# Audio.net
KiCad netlist of a schematic drawn in Altium Designer
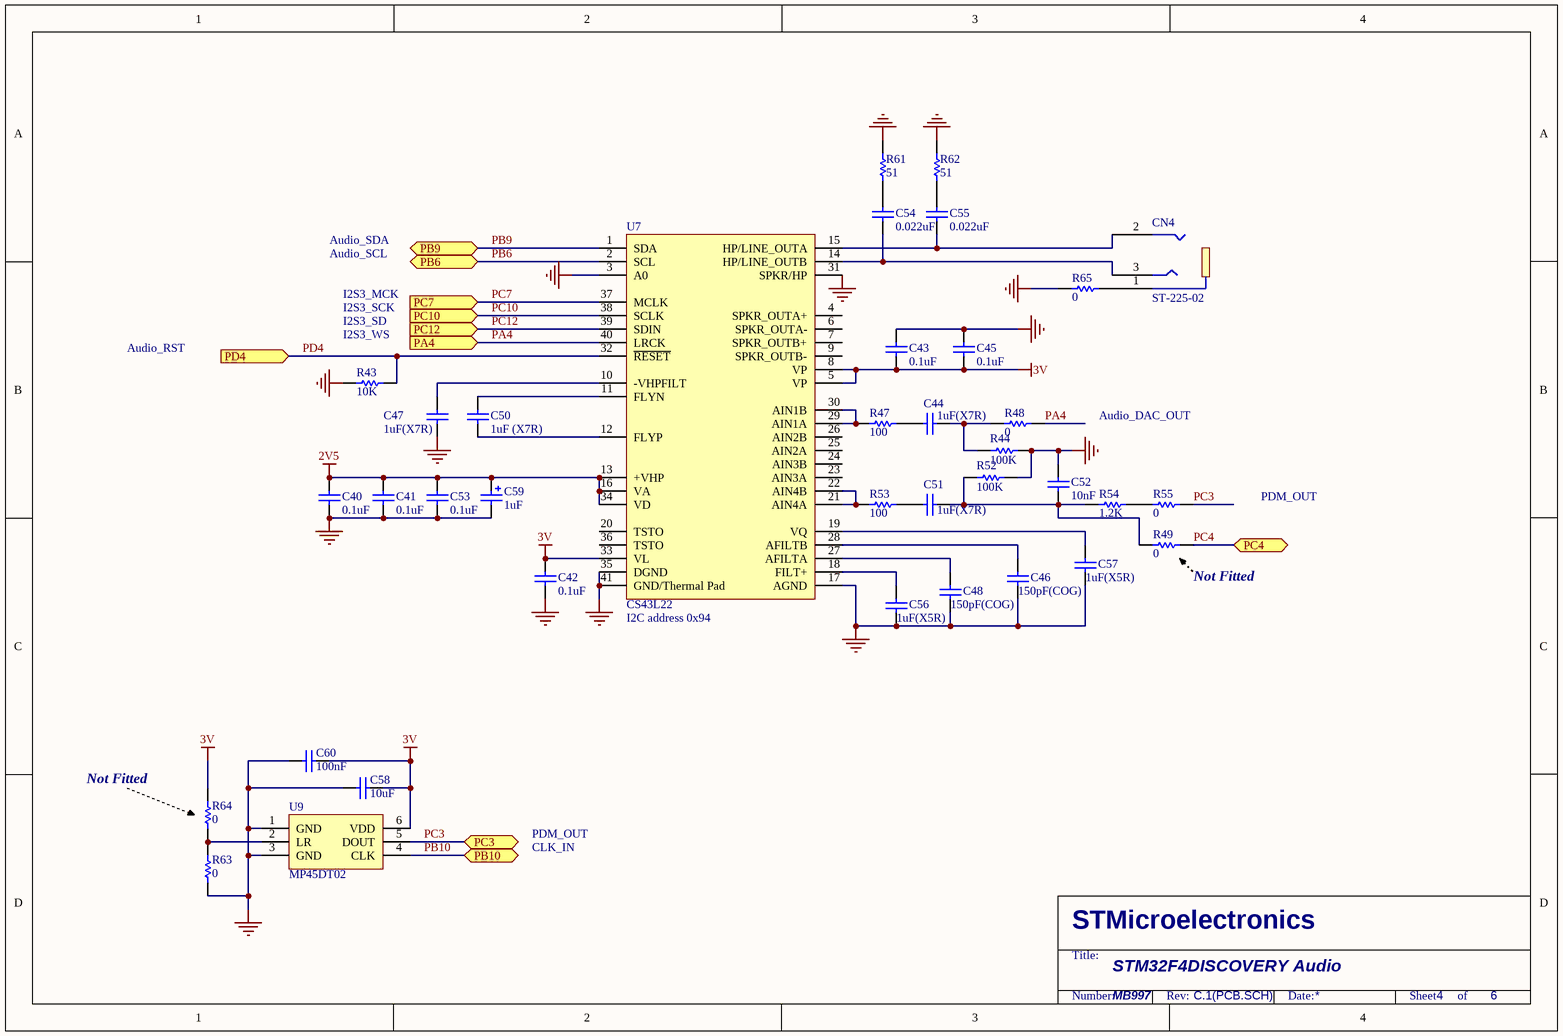
[diagram p0: Audio.SchDoc]

(export (version "E")
  (design (tool "Eeschema 10.0.6"))
  (components
    (comp (ref "C40")
      (value "0.1uF")
      (footprint "0402C")
      (description "Capacitor")
      (fields (field (name "PUBLISHER") "Altium Limited"))
      (libsource (lib "Miscellaneous Devices") (part "CAP"))
    )
    (comp (ref "C41")
      (value "0.1uF")
      (footprint "0402C")
      (description "Capacitor")
      (fields (field (name "PUBLISHER") "Altium Limited"))
      (libsource (lib "Miscellaneous Devices") (part "CAP"))
    )
    (comp (ref "C42")
      (value "0.1uF")
      (footprint "0402C")
      (description "Capacitor")
      (fields (field (name "PUBLISHER") "Altium Limited"))
      (libsource (lib "Miscellaneous Devices") (part "CAP"))
    )
    (comp (ref "C43")
      (value "0.1uF")
      (footprint "0402C")
      (description "Capacitor")
      (fields (field (name "PUBLISHER") "Altium Limited"))
      (libsource (lib "Miscellaneous Devices") (part "CAP"))
    )
    (comp (ref "C44")
      (value "1uF(X7R)")
      (footprint "0603C")
      (description "Capacitor")
      (fields (field (name "PUBLISHER") "Altium Limited"))
      (libsource (lib "Miscellaneous Devices") (part "CAP"))
    )
    (comp (ref "C45")
      (value "0.1uF")
      (footprint "0402C")
      (description "Capacitor")
      (fields (field (name "PUBLISHER") "Altium Limited"))
      (libsource (lib "Miscellaneous Devices") (part "CAP"))
    )
    (comp (ref "C46")
      (value "150pF(COG)")
      (footprint "0603C")
      (description "Capacitor")
      (fields (field (name "PUBLISHER") "Altium Limited"))
      (libsource (lib "Miscellaneous Devices") (part "CAP"))
    )
    (comp (ref "C47")
      (value "1uF(X7R)")
      (footprint "0603C")
      (description "Capacitor")
      (fields (field (name "PUBLISHER") "Altium Limited"))
      (libsource (lib "Miscellaneous Devices") (part "CAP"))
    )
    (comp (ref "C48")
      (value "150pF(COG)")
      (footprint "0603C")
      (description "Capacitor")
      (fields (field (name "PUBLISHER") "Altium Limited"))
      (libsource (lib "Miscellaneous Devices") (part "CAP"))
    )
    (comp (ref "C50")
      (value "1uF (X7R)")
      (footprint "0603C")
      (description "Capacitor")
      (fields (field (name "PUBLISHER") "Altium Limited"))
      (libsource (lib "Miscellaneous Devices") (part "CAP"))
    )
    (comp (ref "C51")
      (value "1uF(X7R)")
      (footprint "0603C")
      (description "Capacitor")
      (fields (field (name "PUBLISHER") "Altium Limited"))
      (libsource (lib "Miscellaneous Devices") (part "CAP"))
    )
    (comp (ref "C52")
      (value "10nF")
      (footprint "0603C")
      (description "Capacitor")
      (fields (field (name "PUBLISHER") "Altium Limited"))
      (libsource (lib "Miscellaneous Devices") (part "CAP"))
    )
    (comp (ref "C53")
      (value "0.1uF")
      (footprint "0402C")
      (description "Capacitor")
      (fields (field (name "PUBLISHER") "Altium Limited"))
      (libsource (lib "Miscellaneous Devices") (part "CAP"))
    )
    (comp (ref "C54")
      (value "0.022uF")
      (footprint "0603C")
      (description "Capacitor")
      (fields (field (name "PUBLISHER") "Altium Limited"))
      (libsource (lib "Miscellaneous Devices") (part "CAP"))
    )
    (comp (ref "C55")
      (value "0.022uF")
      (footprint "0603C")
      (description "Capacitor")
      (fields (field (name "PUBLISHER") "Altium Limited"))
      (libsource (lib "Miscellaneous Devices") (part "CAP"))
    )
    (comp (ref "C56")
      (value "1uF(X5R)")
      (footprint "0603C")
      (description "Capacitor")
      (fields (field (name "PUBLISHER") "Altium Limited"))
      (libsource (lib "Miscellaneous Devices") (part "CAP"))
    )
    (comp (ref "C57")
      (value "1uF(X5R)")
      (footprint "0603C")
      (description "Capacitor")
      (fields (field (name "PUBLISHER") "Altium Limited"))
      (libsource (lib "Miscellaneous Devices") (part "CAP"))
    )
    (comp (ref "C58")
      (value "10uF")
      (footprint "0603C")
      (description "Capacitor")
      (fields (field (name "PUBLISHER") "Altium Limited"))
      (libsource (lib "Miscellaneous Devices") (part "CAP"))
    )
    (comp (ref "C59")
      (value "1uF")
      (footprint "TAN-A")
      (description "Polarized Capacitor (Radial)")
      (fields (field (name "PUBLISHER") "Altium Limited"))
      (libsource (lib "Miscellaneous Devices") (part "Cap Pol1"))
    )
    (comp (ref "C60")
      (value "100nF")
      (footprint "0603C")
      (description "Capacitor")
      (fields (field (name "PUBLISHER") "Altium Limited"))
      (libsource (lib "Miscellaneous Devices") (part "CAP"))
    )
    (comp (ref "CN4")
      (value "ST-225-02")
      (footprint "Jack-ST-225")
      (description "Connector Jack 35mm")
      (libsource (lib "MB997") (part "ST-225-02"))
    )
    (comp (ref "R43")
      (value "10K")
      (footprint "0402R")
      (description "Resistor")
      (fields (field (name "PUBLISHER") "Altium Limited"))
      (libsource (lib "Miscellaneous Devices") (part "res1"))
    )
    (comp (ref "R44")
      (value "100K")
      (footprint "0402R")
      (description "Resistor")
      (fields (field (name "PUBLISHER") "Altium Limited"))
      (libsource (lib "Miscellaneous Devices") (part "res1"))
    )
    (comp (ref "R47")
      (value "100")
      (footprint "0603R")
      (description "Resistor")
      (fields (field (name "PUBLISHER") "Altium Limited"))
      (libsource (lib "Miscellaneous Devices") (part "res1"))
    )
    (comp (ref "R48")
      (value "0")
      (footprint "0402R")
      (description "Resistor")
      (fields (field (name "PUBLISHER") "Altium Limited"))
      (libsource (lib "Miscellaneous Devices") (part "res1"))
    )
    (comp (ref "R49")
      (value "0")
      (footprint "0402R")
      (description "Resistor")
      (fields (field (name "PUBLISHER") "Altium Limited"))
      (libsource (lib "Miscellaneous Devices") (part "res1"))
    )
    (comp (ref "R52")
      (value "100K")
      (footprint "0402R")
      (description "Resistor")
      (fields (field (name "PUBLISHER") "Altium Limited"))
      (libsource (lib "Miscellaneous Devices") (part "res1"))
    )
    (comp (ref "R53")
      (value "100")
      (footprint "0603R")
      (description "Resistor")
      (fields (field (name "PUBLISHER") "Altium Limited"))
      (libsource (lib "Miscellaneous Devices") (part "res1"))
    )
    (comp (ref "R54")
      (value "1.2K")
      (footprint "0603R")
      (description "Resistor")
      (fields (field (name "PUBLISHER") "Altium Limited"))
      (libsource (lib "Miscellaneous Devices") (part "res1"))
    )
    (comp (ref "R55")
      (value "0")
      (footprint "0402R")
      (description "Resistor")
      (fields (field (name "PUBLISHER") "Altium Limited"))
      (libsource (lib "Miscellaneous Devices") (part "res1"))
    )
    (comp (ref "R61")
      (value "51")
      (footprint "0603R")
      (description "Resistor")
      (fields (field (name "PUBLISHER") "Altium Limited"))
      (libsource (lib "Miscellaneous Devices") (part "res1"))
    )
    (comp (ref "R62")
      (value "51")
      (footprint "0603R")
      (description "Resistor")
      (fields (field (name "PUBLISHER") "Altium Limited"))
      (libsource (lib "Miscellaneous Devices") (part "res1"))
    )
    (comp (ref "R63")
      (value "0")
      (footprint "0402R")
      (description "Resistor")
      (fields (field (name "PUBLISHER") "Altium Limited"))
      (libsource (lib "Miscellaneous Devices") (part "res1"))
    )
    (comp (ref "R64")
      (value "0")
      (footprint "0402R")
      (description "Resistor")
      (fields (field (name "PUBLISHER") "Altium Limited"))
      (libsource (lib "Miscellaneous Devices") (part "res1"))
    )
    (comp (ref "R65")
      (value "0")
      (footprint "0402R")
      (description "Resistor")
      (fields (field (name "PUBLISHER") "Altium Limited"))
      (libsource (lib "Miscellaneous Devices") (part "res1"))
    )
    (comp (ref "U7")
      (value "CS43L22")
      (footprint "QFN40")
      (description "Low Power, Stereo DAC w/Headphone & Speaker Amps")
      (libsource (lib "MB997") (part "CS43L22"))
    )
    (comp (ref "U9")
      (value "MP45DT02")
      (footprint "HLGA-4.72-3.76-6LD")
      (description "MEMS audio sensor, omnidirectional digital microphone")
      (libsource (lib "MB997") (part "MP45DT02"))
    )
  )
  (nets
    (net (code "1") (name "/PA4") (class "Default")
      (node (ref "R48") (pin "1") (pinfunction "1_1") (pintype "passive"))
      (node (ref "U7") (pin "40") (pinfunction "LRCK_40") (pintype "passive"))
    )
    (net (code "2") (name "/PB6") (class "Default")
      (node (ref "U7") (pin "2") (pinfunction "SCL_2") (pintype "passive"))
    )
    (net (code "3") (name "/PB9") (class "Default")
      (node (ref "U7") (pin "1") (pinfunction "SDA_1") (pintype "passive"))
    )
    (net (code "4") (name "/PB10") (class "Default")
      (node (ref "U9") (pin "4") (pinfunction "CLK_4") (pintype "passive"))
    )
    (net (code "5") (name "/PC3") (class "Default")
      (node (ref "R55") (pin "1") (pinfunction "1_1") (pintype "passive"))
      (node (ref "U9") (pin "5") (pinfunction "DOUT_5") (pintype "passive"))
    )
    (net (code "6") (name "/PC4") (class "Default")
      (node (ref "R49") (pin "1") (pinfunction "1_1") (pintype "passive"))
    )
    (net (code "7") (name "/PC7") (class "Default")
      (node (ref "U7") (pin "37") (pinfunction "MCLK_37") (pintype "passive"))
    )
    (net (code "8") (name "/PC10") (class "Default")
      (node (ref "U7") (pin "38") (pinfunction "SCLK_38") (pintype "passive"))
    )
    (net (code "9") (name "/PC12") (class "Default")
      (node (ref "U7") (pin "39") (pinfunction "SDIN_39") (pintype "passive"))
    )
    (net (code "10") (name "/PD4") (class "Default")
      (node (ref "R43") (pin "1") (pinfunction "1_1") (pintype "passive"))
      (node (ref "U7") (pin "32") (pinfunction "~{RESET}_32") (pintype "passive"))
    )
    (net (code "11") (name "2V5") (class "Default")
      (node (ref "C40") (pin "2") (pinfunction "2_2") (pintype "passive"))
      (node (ref "C41") (pin "2") (pinfunction "2_2") (pintype "passive"))
      (node (ref "C53") (pin "2") (pinfunction "2_2") (pintype "passive"))
      (node (ref "C59") (pin "1") (pinfunction "1_1") (pintype "passive"))
      (node (ref "U7") (pin "13") (pinfunction "+VHP_13") (pintype "passive"))
      (node (ref "U7") (pin "16") (pinfunction "VA_16") (pintype "passive"))
      (node (ref "U7") (pin "34") (pinfunction "VD_34") (pintype "passive"))
    )
    (net (code "12") (name "3V") (class "Default")
      (node (ref "C42") (pin "2") (pinfunction "2_2") (pintype "passive"))
      (node (ref "C43") (pin "2") (pinfunction "2_2") (pintype "passive"))
      (node (ref "C45") (pin "2") (pinfunction "2_2") (pintype "passive"))
      (node (ref "C58") (pin "2") (pinfunction "2_2") (pintype "passive"))
      (node (ref "C60") (pin "2") (pinfunction "2_2") (pintype "passive"))
      (node (ref "R64") (pin "2") (pinfunction "2_2") (pintype "passive"))
      (node (ref "U7") (pin "33") (pinfunction "VL_33") (pintype "passive"))
      (node (ref "U7") (pin "5") (pinfunction "VP_5") (pintype "passive"))
      (node (ref "U7") (pin "8") (pinfunction "VP_8") (pintype "passive"))
      (node (ref "U9") (pin "6") (pinfunction "VDD_6") (pintype "power_in"))
    )
    (net (code "13") (name "GND") (class "Default")
      (node (ref "C40") (pin "1") (pinfunction "1_1") (pintype "passive"))
      (node (ref "C41") (pin "1") (pinfunction "1_1") (pintype "passive"))
      (node (ref "C42") (pin "1") (pinfunction "1_1") (pintype "passive"))
      (node (ref "C43") (pin "1") (pinfunction "1_1") (pintype "passive"))
      (node (ref "C45") (pin "1") (pinfunction "1_1") (pintype "passive"))
      (node (ref "C46") (pin "1") (pinfunction "1_1") (pintype "passive"))
      (node (ref "C47") (pin "2") (pinfunction "2_2") (pintype "passive"))
      (node (ref "C48") (pin "1") (pinfunction "1_1") (pintype "passive"))
      (node (ref "C52") (pin "2") (pinfunction "2_2") (pintype "passive"))
      (node (ref "C53") (pin "1") (pinfunction "1_1") (pintype "passive"))
      (node (ref "C56") (pin "1") (pinfunction "1_1") (pintype "passive"))
      (node (ref "C57") (pin "1") (pinfunction "1_1") (pintype "passive"))
      (node (ref "C58") (pin "1") (pinfunction "1_1") (pintype "passive"))
      (node (ref "C59") (pin "2") (pinfunction "2_2") (pintype "passive"))
      (node (ref "C60") (pin "1") (pinfunction "1_1") (pintype "passive"))
      (node (ref "R43") (pin "2") (pinfunction "2_2") (pintype "passive"))
      (node (ref "R44") (pin "2") (pinfunction "2_2") (pintype "passive"))
      (node (ref "R52") (pin "2") (pinfunction "2_2") (pintype "passive"))
      (node (ref "R61") (pin "1") (pinfunction "1_1") (pintype "passive"))
      (node (ref "R62") (pin "1") (pinfunction "1_1") (pintype "passive"))
      (node (ref "R63") (pin "1") (pinfunction "1_1") (pintype "passive"))
      (node (ref "R65") (pin "2") (pinfunction "2_2") (pintype "passive"))
      (node (ref "U7") (pin "17") (pinfunction "AGND_17") (pintype "passive"))
      (node (ref "U7") (pin "3") (pinfunction "A0_3") (pintype "passive"))
      (node (ref "U7") (pin "31") (pinfunction "SPKR/HP_31") (pintype "passive"))
      (node (ref "U7") (pin "35") (pinfunction "DGND_35") (pintype "passive"))
      (node (ref "U7") (pin "41") (pinfunction "GND/Thermal_Pad_41") (pintype "passive"))
      (node (ref "U9") (pin "1") (pinfunction "GND_1") (pintype "passive"))
      (node (ref "U9") (pin "3") (pinfunction "GND_3") (pintype "passive"))
    )
    (net (code "14") (name "Net-(C44-Pad1)") (class "Default")
      (node (ref "C44") (pin "1") (pinfunction "1_1") (pintype "passive"))
      (node (ref "R47") (pin "1") (pinfunction "1_1") (pintype "passive"))
    )
    (net (code "15") (name "Net-(C44-Pad2)") (class "Default")
      (node (ref "C44") (pin "2") (pinfunction "2_2") (pintype "passive"))
      (node (ref "R44") (pin "1") (pinfunction "1_1") (pintype "passive"))
      (node (ref "R48") (pin "2") (pinfunction "2_2") (pintype "passive"))
    )
    (net (code "16") (name "Net-(C51-Pad1)") (class "Default")
      (node (ref "C51") (pin "1") (pinfunction "1_1") (pintype "passive"))
      (node (ref "R53") (pin "1") (pinfunction "1_1") (pintype "passive"))
    )
    (net (code "17") (name "Net-(C51-Pad2)") (class "Default")
      (node (ref "C51") (pin "2") (pinfunction "2_2") (pintype "passive"))
      (node (ref "C52") (pin "1") (pinfunction "1_1") (pintype "passive"))
      (node (ref "R49") (pin "2") (pinfunction "2_2") (pintype "passive"))
      (node (ref "R52") (pin "1") (pinfunction "1_1") (pintype "passive"))
      (node (ref "R54") (pin "1") (pinfunction "1_1") (pintype "passive"))
    )
    (net (code "18") (name "Net-(C54-Pad1)") (class "Default")
      (node (ref "C54") (pin "1") (pinfunction "1_1") (pintype "passive"))
      (node (ref "R61") (pin "2") (pinfunction "2_2") (pintype "passive"))
    )
    (net (code "19") (name "Net-(C55-Pad1)") (class "Default")
      (node (ref "C55") (pin "1") (pinfunction "1_1") (pintype "passive"))
      (node (ref "R62") (pin "2") (pinfunction "2_2") (pintype "passive"))
    )
    (net (code "20") (name "Net-(CN4-Pad1)") (class "Default")
      (node (ref "CN4") (pin "1") (pintype "passive"))
      (node (ref "R65") (pin "1") (pinfunction "1_1") (pintype "passive"))
    )
    (net (code "21") (name "Net-(R54-Pad2)") (class "Default")
      (node (ref "R54") (pin "2") (pinfunction "2_2") (pintype "passive"))
      (node (ref "R55") (pin "2") (pinfunction "2_2") (pintype "passive"))
    )
    (net (code "22") (name "Net-(U7--VHPFILT)") (class "Default")
      (node (ref "C47") (pin "1") (pinfunction "1_1") (pintype "passive"))
      (node (ref "U7") (pin "10") (pinfunction "-VHPFILT_10") (pintype "passive"))
    )
    (net (code "23") (name "Net-(U7-AFILTA)") (class "Default")
      (node (ref "C48") (pin "2") (pinfunction "2_2") (pintype "passive"))
      (node (ref "U7") (pin "27") (pinfunction "AFILTA_27") (pintype "passive"))
    )
    (net (code "24") (name "Net-(U7-AFILTB)") (class "Default")
      (node (ref "C46") (pin "2") (pinfunction "2_2") (pintype "passive"))
      (node (ref "U7") (pin "28") (pinfunction "AFILTB_28") (pintype "passive"))
    )
    (net (code "25") (name "Net-(U7-AIN1A)") (class "Default")
      (node (ref "R47") (pin "2") (pinfunction "2_2") (pintype "passive"))
      (node (ref "U7") (pin "29") (pinfunction "AIN1A_29") (pintype "passive"))
      (node (ref "U7") (pin "30") (pinfunction "AIN1B_30") (pintype "passive"))
    )
    (net (code "26") (name "Net-(U7-AIN4A)") (class "Default")
      (node (ref "R53") (pin "2") (pinfunction "2_2") (pintype "passive"))
      (node (ref "U7") (pin "21") (pinfunction "AIN4A_21") (pintype "passive"))
      (node (ref "U7") (pin "22") (pinfunction "AIN4B_22") (pintype "passive"))
    )
    (net (code "27") (name "Net-(U7-FILT+)") (class "Default")
      (node (ref "C56") (pin "2") (pinfunction "2_2") (pintype "passive"))
      (node (ref "U7") (pin "18") (pinfunction "FILT+_18") (pintype "passive"))
    )
    (net (code "28") (name "Net-(U7-FLYN)") (class "Default")
      (node (ref "C50") (pin "2") (pinfunction "2_2") (pintype "passive"))
      (node (ref "U7") (pin "11") (pinfunction "FLYN_11") (pintype "passive"))
    )
    (net (code "29") (name "Net-(U7-FLYP)") (class "Default")
      (node (ref "C50") (pin "1") (pinfunction "1_1") (pintype "passive"))
      (node (ref "U7") (pin "12") (pinfunction "FLYP_12") (pintype "passive"))
    )
    (net (code "30") (name "Net-(U7-HP{slash}LINE_OUTA)") (class "Default")
      (node (ref "C55") (pin "2") (pinfunction "2_2") (pintype "passive"))
      (node (ref "CN4") (pin "2") (pintype "passive"))
      (node (ref "U7") (pin "15") (pinfunction "HP/LINE_OUTA_15") (pintype "passive"))
    )
    (net (code "31") (name "Net-(U7-HP{slash}LINE_OUTB)") (class "Default")
      (node (ref "C54") (pin "2") (pinfunction "2_2") (pintype "passive"))
      (node (ref "CN4") (pin "3") (pintype "passive"))
      (node (ref "U7") (pin "14") (pinfunction "HP/LINE_OUTB_14") (pintype "passive"))
    )
    (net (code "32") (name "Net-(U7-VQ)") (class "Default")
      (node (ref "C57") (pin "2") (pinfunction "2_2") (pintype "passive"))
      (node (ref "U7") (pin "19") (pinfunction "VQ_19") (pintype "passive"))
    )
    (net (code "33") (name "Net-(U9-LR)") (class "Default")
      (node (ref "R63") (pin "2") (pinfunction "2_2") (pintype "passive"))
      (node (ref "R64") (pin "1") (pinfunction "1_1") (pintype "passive"))
      (node (ref "U9") (pin "2") (pinfunction "LR_2") (pintype "passive"))
    )
    (net (code "34") (name "unconnected-(U7-AIN2A-Pad25)") (class "Default")
      (node (ref "U7") (pin "25") (pinfunction "AIN2A_25") (pintype "passive"))
    )
    (net (code "35") (name "unconnected-(U7-AIN2B-Pad26)") (class "Default")
      (node (ref "U7") (pin "26") (pinfunction "AIN2B_26") (pintype "passive"))
    )
    (net (code "36") (name "unconnected-(U7-AIN3A-Pad23)") (class "Default")
      (node (ref "U7") (pin "23") (pinfunction "AIN3A_23") (pintype "passive"))
    )
    (net (code "37") (name "unconnected-(U7-AIN3B-Pad24)") (class "Default")
      (node (ref "U7") (pin "24") (pinfunction "AIN3B_24") (pintype "passive"))
    )
    (net (code "38") (name "unconnected-(U7-SPKR_OUTA+-Pad4)") (class "Default")
      (node (ref "U7") (pin "4") (pinfunction "SPKR_OUTA+_4") (pintype "passive"))
    )
    (net (code "39") (name "unconnected-(U7-SPKR_OUTA--Pad6)") (class "Default")
      (node (ref "U7") (pin "6") (pinfunction "SPKR_OUTA-_6") (pintype "passive"))
    )
    (net (code "40") (name "unconnected-(U7-SPKR_OUTB+-Pad7)") (class "Default")
      (node (ref "U7") (pin "7") (pinfunction "SPKR_OUTB+_7") (pintype "passive"))
    )
    (net (code "41") (name "unconnected-(U7-SPKR_OUTB--Pad9)") (class "Default")
      (node (ref "U7") (pin "9") (pinfunction "SPKR_OUTB-_9") (pintype "passive"))
    )
    (net (code "42") (name "unconnected-(U7-TSTO-Pad20)") (class "Default")
      (node (ref "U7") (pin "20") (pinfunction "TSTO_20") (pintype "passive"))
    )
    (net (code "43") (name "unconnected-(U7-TSTO-Pad36)") (class "Default")
      (node (ref "U7") (pin "36") (pinfunction "TSTO_36") (pintype "passive"))
    )
  )
)
